# Esquema.net
KiCad netlist of a schematic drawn in EAGLE
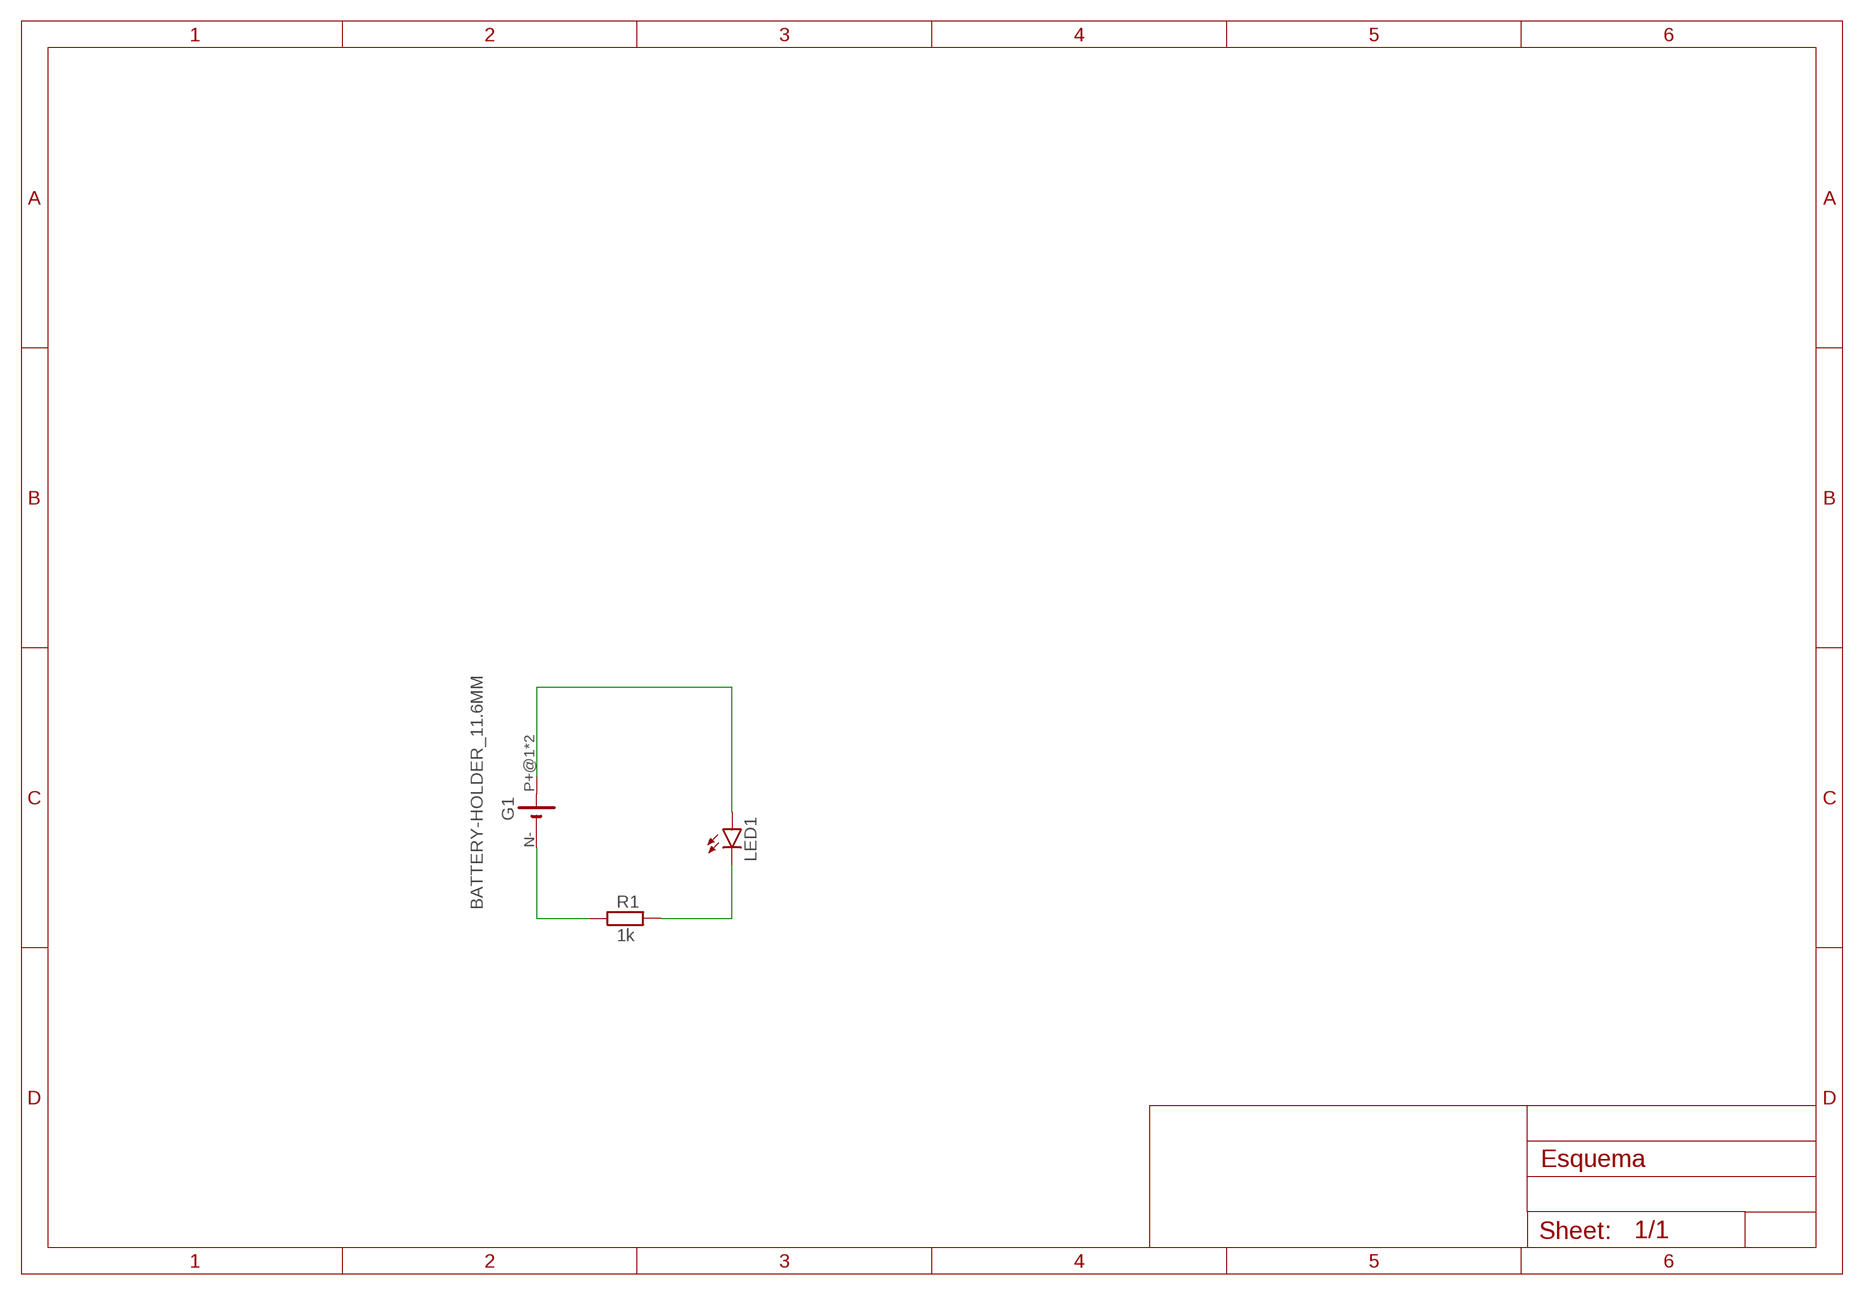
[diagram p0: schematic, sheet 1]

(export (version "E")
  (design (tool "Eeschema 10.0.6"))
  (components
    (comp (ref "G1")
      (value "BATTERY-HOLDER_11.6MM")
      (footprint "eagle-import:CELL_RETAINER_11.6MM")
      (fields (field (name "MF") "KEYSTONE") (field (name "MPN") "2997"))
      (libsource (lib "eagle-import") (part "BATTERY-HOLDER_11.6MM"))
    )
    (comp (ref "LED1")
      (value "LED5MM")
      (footprint "eagle-import:LED5MM")
      (libsource (lib "eagle-import") (part "LED5MM"))
    )
    (comp (ref "R1")
      (value "1k")
      (footprint "eagle-import:0207_10")
      (libsource (lib "eagle-import") (part "R-EU_0207/10"))
    )
  )
  (nets
    (net (code "1") (name "Net-(G1-+-PadP+@1)") (class "Default")
      (node (ref "G1") (pin "P+@1") (pinfunction "+_P+@1") (pintype "passive"))
      (node (ref "G1") (pin "P+@2") (pinfunction "+_P+@2") (pintype "passive"))
      (node (ref "LED1") (pin "A") (pinfunction "A_A") (pintype "passive"))
    )
    (net (code "2") (name "Net-(G1--)") (class "Default")
      (node (ref "G1") (pin "N-") (pinfunction "-_N-") (pintype "passive"))
      (node (ref "R1") (pin "1") (pinfunction "1_1") (pintype "passive"))
    )
    (net (code "3") (name "Net-(LED1-C)") (class "Default")
      (node (ref "LED1") (pin "K") (pinfunction "C_K") (pintype "passive"))
      (node (ref "R1") (pin "2") (pinfunction "2_2") (pintype "passive"))
    )
  )
)
